# v2_schematic.net
KiCad netlist of a schematic drawn in EAGLE
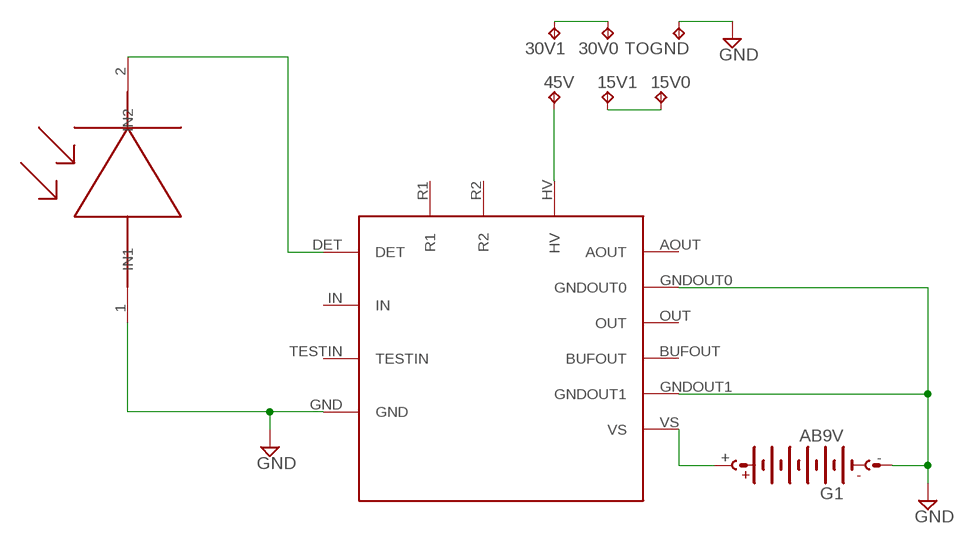
[diagram p0: schematic, sheet 1]

(export (version "E")
  (design (tool "Eeschema 10.0.6"))
  (components
    (comp (ref "15V0")
      (value "TP-063")
      (footprint "eagle-import:TP-063")
      (libsource (lib "eagle-import") (part "TP-063"))
    )
    (comp (ref "15V1")
      (value "TP-063")
      (footprint "eagle-import:TP-063")
      (libsource (lib "eagle-import") (part "TP-063"))
    )
    (comp (ref "30V0")
      (value "TP-063")
      (footprint "eagle-import:TP-063")
      (libsource (lib "eagle-import") (part "TP-063"))
    )
    (comp (ref "30V1")
      (value "TP-063")
      (footprint "eagle-import:TP-063")
      (libsource (lib "eagle-import") (part "TP-063"))
    )
    (comp (ref "45V")
      (value "TP-063")
      (footprint "eagle-import:TP-063")
      (libsource (lib "eagle-import") (part "TP-063"))
    )
    (comp (ref "G1")
      (value "AB9V")
      (footprint "eagle-import:AB9V")
      (libsource (lib "eagle-import") (part "AB9V"))
    )
    (comp (ref "PC21")
      (value "A111")
      (footprint "eagle-import:A111")
      (libsource (lib "eagle-import") (part "A111"))
    )
    (comp (ref "PINDIODE")
      (value "S3590-08")
      (footprint "eagle-import:S3590-08")
      (libsource (lib "eagle-import") (part "S3590-08"))
    )
    (comp (ref "TOGND")
      (value "TP-063")
      (footprint "eagle-import:TP-063")
      (libsource (lib "eagle-import") (part "TP-063"))
    )
  )
  (nets
    (net (code "1") (name "GND") (class "Default")
      (node (ref "G1") (pin "-") (pinfunction "-_-") (pintype "passive"))
      (node (ref "PC21") (pin "GND") (pinfunction "GND_GND") (pintype "bidirectional"))
      (node (ref "PC21") (pin "GNDOUT0") (pinfunction "GNDOUT0_GNDOUT0") (pintype "bidirectional"))
      (node (ref "PC21") (pin "GNDOUT1") (pinfunction "GNDOUT1_GNDOUT1") (pintype "bidirectional"))
      (node (ref "PINDIODE") (pin "1") (pinfunction "IN1_1") (pintype "bidirectional"))
      (node (ref "TOGND") (pin "1") (pinfunction "1_1") (pintype "passive"))
    )
    (net (code "2") (name "Net-(15V0-Pad1)") (class "Default")
      (node (ref "15V0") (pin "1") (pinfunction "1_1") (pintype "passive"))
      (node (ref "15V1") (pin "1") (pinfunction "1_1") (pintype "passive"))
    )
    (net (code "3") (name "Net-(30V0-Pad1)") (class "Default")
      (node (ref "30V0") (pin "1") (pinfunction "1_1") (pintype "passive"))
      (node (ref "30V1") (pin "1") (pinfunction "1_1") (pintype "passive"))
    )
    (net (code "4") (name "Net-(45V-Pad1)") (class "Default")
      (node (ref "45V") (pin "1") (pinfunction "1_1") (pintype "passive"))
      (node (ref "PC21") (pin "HV") (pinfunction "HV_HV") (pintype "bidirectional"))
    )
    (net (code "5") (name "Net-(G1-Pad+)") (class "Default")
      (node (ref "G1") (pin "+") (pinfunction "+_+") (pintype "passive"))
      (node (ref "PC21") (pin "VS") (pinfunction "VS_VS") (pintype "bidirectional"))
    )
    (net (code "6") (name "Net-(PINDIODE-IN2)") (class "Default")
      (node (ref "PC21") (pin "DET") (pinfunction "DET_DET") (pintype "bidirectional"))
      (node (ref "PINDIODE") (pin "2") (pinfunction "IN2_2") (pintype "bidirectional"))
    )
    (net (code "7") (name "unconnected-(PC21-PadAOUT)") (class "Default")
      (node (ref "PC21") (pin "AOUT") (pinfunction "AOUT_AOUT") (pintype "bidirectional"))
    )
    (net (code "8") (name "unconnected-(PC21-PadBUFOUT)") (class "Default")
      (node (ref "PC21") (pin "BUFOUT") (pinfunction "BUFOUT_BUFOUT") (pintype "bidirectional"))
    )
    (net (code "9") (name "unconnected-(PC21-PadIN)") (class "Default")
      (node (ref "PC21") (pin "IN") (pinfunction "IN_IN") (pintype "bidirectional"))
    )
    (net (code "10") (name "unconnected-(PC21-PadOUT)") (class "Default")
      (node (ref "PC21") (pin "OUT") (pinfunction "OUT_OUT") (pintype "bidirectional"))
    )
    (net (code "11") (name "unconnected-(PC21-PadR1)") (class "Default")
      (node (ref "PC21") (pin "R1") (pinfunction "R1_R1") (pintype "bidirectional"))
    )
    (net (code "12") (name "unconnected-(PC21-PadR2)") (class "Default")
      (node (ref "PC21") (pin "R2") (pinfunction "R2_R2") (pintype "bidirectional"))
    )
    (net (code "13") (name "unconnected-(PC21-PadTESTIN)") (class "Default")
      (node (ref "PC21") (pin "TESTIN") (pinfunction "TESTIN_TESTIN") (pintype "bidirectional"))
    )
  )
)
